# nano-master.net
KiCad netlist of a schematic drawn in EAGLE
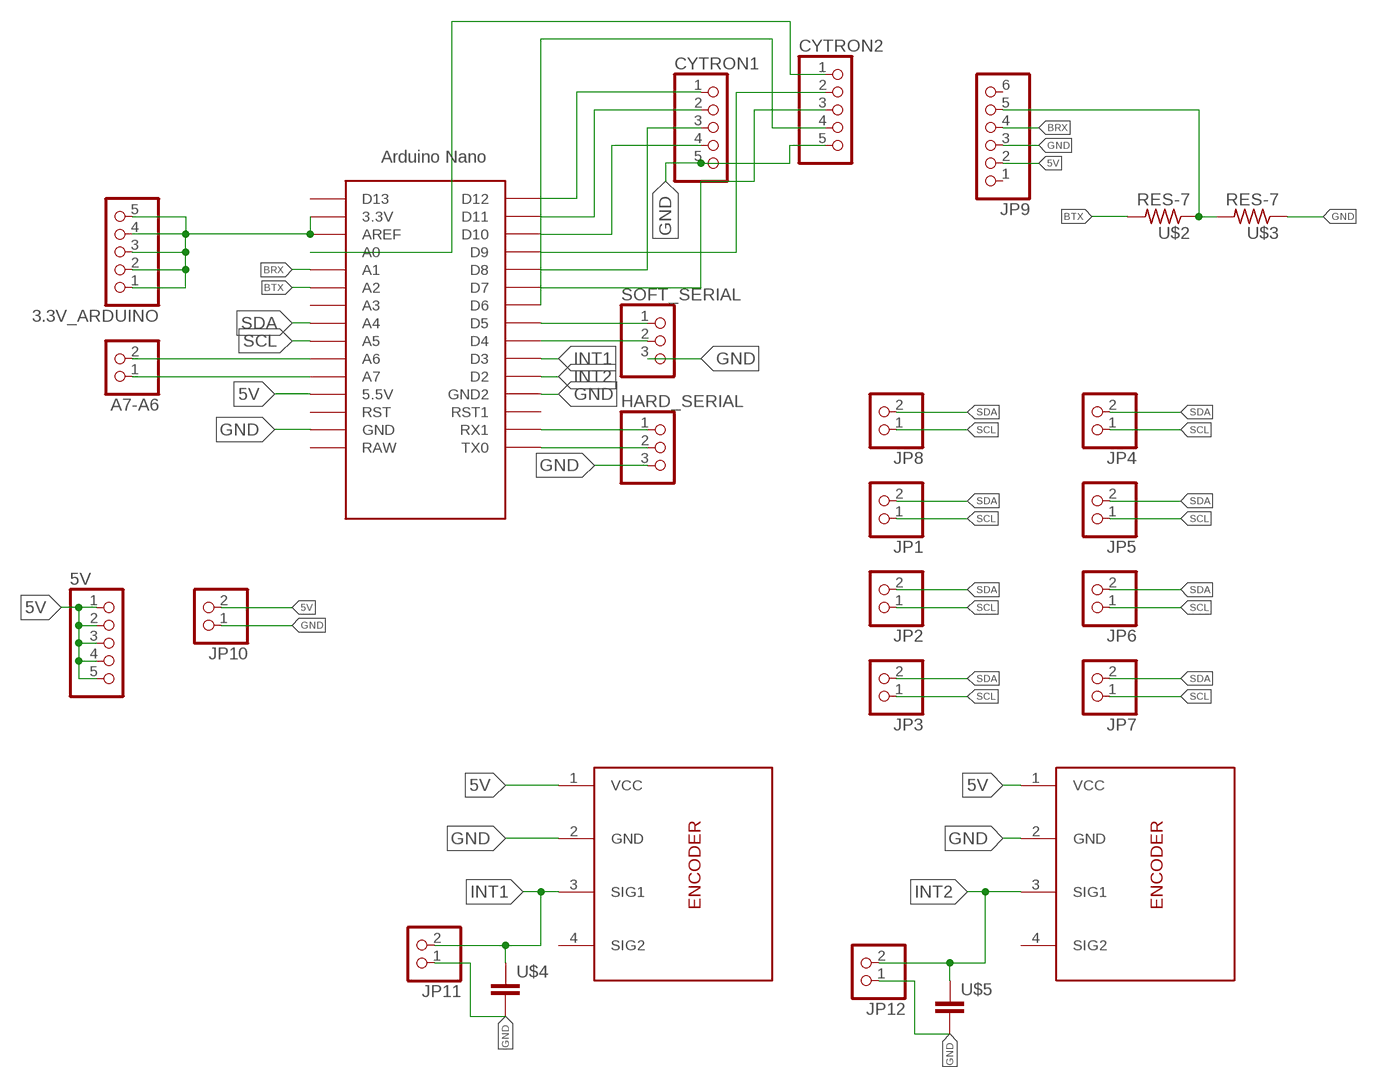
[diagram p0: schematic, sheet 1]

(export (version "E")
  (design (tool "Eeschema 10.0.6"))
  (components
    (comp (ref "3.3V_ARDUINO")
      (value "PINHD-1X5")
      (footprint "eagle-import:1X05")
      (libsource (lib "eagle-import") (part "PINHD-1X5"))
    )
    (comp (ref "5V")
      (value "PINHD-1X5")
      (footprint "eagle-import:1X05")
      (libsource (lib "eagle-import") (part "PINHD-1X5"))
    )
    (comp (ref "A7-A6")
      (value "PINHD-1X2")
      (footprint "eagle-import:1X02")
      (libsource (lib "eagle-import") (part "PINHD-1X2"))
    )
    (comp (ref "CYTRON1")
      (value "PINHD-1X5")
      (footprint "eagle-import:1X05")
      (libsource (lib "eagle-import") (part "PINHD-1X5"))
    )
    (comp (ref "CYTRON2")
      (value "PINHD-1X5")
      (footprint "eagle-import:1X05")
      (libsource (lib "eagle-import") (part "PINHD-1X5"))
    )
    (comp (ref "ENCODER1")
      (value "ENCODER")
      (footprint "eagle-import:1X04_DATA")
      (libsource (lib "eagle-import") (part "ENCODER"))
    )
    (comp (ref "ENCODER2")
      (value "ENCODER")
      (footprint "eagle-import:1X04_DATA")
      (libsource (lib "eagle-import") (part "ENCODER"))
    )
    (comp (ref "HARD_SERIAL")
      (value "PINHD-1X3")
      (footprint "eagle-import:1X03")
      (libsource (lib "eagle-import") (part "PINHD-1X3"))
    )
    (comp (ref "JP1")
      (value "PINHD-1X2")
      (footprint "eagle-import:1X02")
      (libsource (lib "eagle-import") (part "PINHD-1X2"))
    )
    (comp (ref "JP2")
      (value "PINHD-1X2")
      (footprint "eagle-import:1X02")
      (libsource (lib "eagle-import") (part "PINHD-1X2"))
    )
    (comp (ref "JP3")
      (value "PINHD-1X2")
      (footprint "eagle-import:1X02")
      (libsource (lib "eagle-import") (part "PINHD-1X2"))
    )
    (comp (ref "JP4")
      (value "PINHD-1X2")
      (footprint "eagle-import:1X02")
      (libsource (lib "eagle-import") (part "PINHD-1X2"))
    )
    (comp (ref "JP5")
      (value "PINHD-1X2")
      (footprint "eagle-import:1X02")
      (libsource (lib "eagle-import") (part "PINHD-1X2"))
    )
    (comp (ref "JP6")
      (value "PINHD-1X2")
      (footprint "eagle-import:1X02")
      (libsource (lib "eagle-import") (part "PINHD-1X2"))
    )
    (comp (ref "JP7")
      (value "PINHD-1X2")
      (footprint "eagle-import:1X02")
      (libsource (lib "eagle-import") (part "PINHD-1X2"))
    )
    (comp (ref "JP8")
      (value "PINHD-1X2")
      (footprint "eagle-import:1X02")
      (libsource (lib "eagle-import") (part "PINHD-1X2"))
    )
    (comp (ref "JP9")
      (value "PINHD-1X6")
      (footprint "eagle-import:1X06")
      (libsource (lib "eagle-import") (part "PINHD-1X6"))
    )
    (comp (ref "JP10")
      (value "PINHD-1X2")
      (footprint "eagle-import:1X02")
      (libsource (lib "eagle-import") (part "PINHD-1X2"))
    )
    (comp (ref "JP11")
      (value "PINHD-1X2")
      (footprint "eagle-import:1X02")
      (libsource (lib "eagle-import") (part "PINHD-1X2"))
    )
    (comp (ref "JP12")
      (value "PINHD-1X2")
      (footprint "eagle-import:1X02")
      (libsource (lib "eagle-import") (part "PINHD-1X2"))
    )
    (comp (ref "SOFT_SERIAL")
      (value "PINHD-1X3")
      (footprint "eagle-import:1X03")
      (libsource (lib "eagle-import") (part "PINHD-1X3"))
    )
    (comp (ref "U$1")
      (value "ARDUINO_NANO")
      (footprint "eagle-import:NANO")
      (libsource (lib "eagle-import") (part "ARDUINO_NANO"))
    )
    (comp (ref "U$2")
      (value "RES-7")
      (footprint "eagle-import:0204_7")
      (libsource (lib "eagle-import") (part "RES-7"))
    )
    (comp (ref "U$3")
      (value "RES-7")
      (footprint "eagle-import:0204_7")
      (libsource (lib "eagle-import") (part "RES-7"))
    )
    (comp (ref "U$4")
      (value "CAPACITOR")
      (footprint "eagle-import:C025-025X050")
      (libsource (lib "eagle-import") (part "CAPACITOR"))
    )
    (comp (ref "U$5")
      (value "CAPACITOR")
      (footprint "eagle-import:C025-025X050")
      (libsource (lib "eagle-import") (part "CAPACITOR"))
    )
  )
  (nets
    (net (code "1") (name "5V") (class "Default")
      (node (ref "5V") (pin "1") (pinfunction "1_1") (pintype "passive"))
      (node (ref "5V") (pin "2") (pinfunction "2_2") (pintype "passive"))
      (node (ref "5V") (pin "3") (pinfunction "3_3") (pintype "passive"))
      (node (ref "5V") (pin "4") (pinfunction "4_4") (pintype "passive"))
      (node (ref "5V") (pin "5") (pinfunction "5_5") (pintype "passive"))
      (node (ref "ENCODER1") (pin "1") (pinfunction "VCC_1") (pintype "bidirectional"))
      (node (ref "ENCODER2") (pin "1") (pinfunction "VCC_1") (pintype "bidirectional"))
      (node (ref "JP10") (pin "2") (pinfunction "2_2") (pintype "passive"))
      (node (ref "JP9") (pin "2") (pinfunction "2_2") (pintype "passive"))
      (node (ref "U$1") (pin "5V") (pinfunction "5.5V_5V") (pintype "bidirectional"))
    )
    (net (code "2") (name "BRX") (class "Default")
      (node (ref "JP9") (pin "4") (pinfunction "4_4") (pintype "passive"))
      (node (ref "U$1") (pin "A1") (pinfunction "A1_A1") (pintype "bidirectional"))
    )
    (net (code "3") (name "BTX") (class "Default")
      (node (ref "U$1") (pin "A2") (pinfunction "A2_A2") (pintype "bidirectional"))
      (node (ref "U$2") (pin "2") (pinfunction "2_2") (pintype "passive"))
    )
    (net (code "4") (name "GND") (class "Default")
      (node (ref "CYTRON1") (pin "5") (pinfunction "5_5") (pintype "passive"))
      (node (ref "CYTRON2") (pin "5") (pinfunction "5_5") (pintype "passive"))
      (node (ref "ENCODER1") (pin "2") (pinfunction "GND_2") (pintype "bidirectional"))
      (node (ref "ENCODER2") (pin "2") (pinfunction "GND_2") (pintype "bidirectional"))
      (node (ref "HARD_SERIAL") (pin "3") (pinfunction "3_3") (pintype "passive"))
      (node (ref "JP10") (pin "1") (pinfunction "1_1") (pintype "passive"))
      (node (ref "JP11") (pin "1") (pinfunction "1_1") (pintype "passive"))
      (node (ref "JP12") (pin "1") (pinfunction "1_1") (pintype "passive"))
      (node (ref "JP9") (pin "3") (pinfunction "3_3") (pintype "passive"))
      (node (ref "SOFT_SERIAL") (pin "3") (pinfunction "3_3") (pintype "passive"))
      (node (ref "U$1") (pin "GND") (pinfunction "GND_GND") (pintype "bidirectional"))
      (node (ref "U$1") (pin "GND1") (pinfunction "GND2_GND1") (pintype "bidirectional"))
      (node (ref "U$3") (pin "1") (pinfunction "1_1") (pintype "passive"))
      (node (ref "U$4") (pin "2") (pinfunction "2_2") (pintype "passive"))
      (node (ref "U$5") (pin "2") (pinfunction "2_2") (pintype "passive"))
    )
    (net (code "5") (name "INT1") (class "Default")
      (node (ref "ENCODER2") (pin "3") (pinfunction "SIG1_3") (pintype "bidirectional"))
      (node (ref "JP11") (pin "2") (pinfunction "2_2") (pintype "passive"))
      (node (ref "U$1") (pin "D3") (pinfunction "D3_D3") (pintype "bidirectional"))
      (node (ref "U$4") (pin "1") (pinfunction "1_1") (pintype "passive"))
    )
    (net (code "6") (name "INT2") (class "Default")
      (node (ref "ENCODER1") (pin "3") (pinfunction "SIG1_3") (pintype "bidirectional"))
      (node (ref "JP12") (pin "2") (pinfunction "2_2") (pintype "passive"))
      (node (ref "U$1") (pin "D2") (pinfunction "D2_D2") (pintype "bidirectional"))
      (node (ref "U$5") (pin "1") (pinfunction "1_1") (pintype "passive"))
    )
    (net (code "7") (name "Net-(3.3V_ARDUINO-Pad1)") (class "Default")
      (node (ref "3.3V_ARDUINO") (pin "1") (pinfunction "1_1") (pintype "passive"))
      (node (ref "3.3V_ARDUINO") (pin "2") (pinfunction "2_2") (pintype "passive"))
      (node (ref "3.3V_ARDUINO") (pin "3") (pinfunction "3_3") (pintype "passive"))
      (node (ref "3.3V_ARDUINO") (pin "4") (pinfunction "4_4") (pintype "passive"))
      (node (ref "3.3V_ARDUINO") (pin "5") (pinfunction "5_5") (pintype "passive"))
      (node (ref "U$1") (pin "3.3V") (pinfunction "3.3V_3.3V") (pintype "bidirectional"))
      (node (ref "U$1") (pin "AREF") (pinfunction "AREF_AREF") (pintype "bidirectional"))
    )
    (net (code "8") (name "Net-(A7-A6-Pad1)") (class "Default")
      (node (ref "A7-A6") (pin "1") (pinfunction "1_1") (pintype "passive"))
      (node (ref "U$1") (pin "A7") (pinfunction "A7_A7") (pintype "bidirectional"))
    )
    (net (code "9") (name "Net-(A7-A6-Pad2)") (class "Default")
      (node (ref "A7-A6") (pin "2") (pinfunction "2_2") (pintype "passive"))
      (node (ref "U$1") (pin "A6") (pinfunction "A6_A6") (pintype "bidirectional"))
    )
    (net (code "10") (name "Net-(CYTRON1-Pad1)") (class "Default")
      (node (ref "CYTRON1") (pin "1") (pinfunction "1_1") (pintype "passive"))
      (node (ref "U$1") (pin "D12") (pinfunction "D12_D12") (pintype "bidirectional"))
    )
    (net (code "11") (name "Net-(CYTRON1-Pad2)") (class "Default")
      (node (ref "CYTRON1") (pin "2") (pinfunction "2_2") (pintype "passive"))
      (node (ref "U$1") (pin "D11") (pinfunction "D11_D11") (pintype "bidirectional"))
    )
    (net (code "12") (name "Net-(CYTRON1-Pad3)") (class "Default")
      (node (ref "CYTRON1") (pin "3") (pinfunction "3_3") (pintype "passive"))
      (node (ref "U$1") (pin "D8") (pinfunction "D8_D8") (pintype "bidirectional"))
    )
    (net (code "13") (name "Net-(CYTRON1-Pad4)") (class "Default")
      (node (ref "CYTRON1") (pin "4") (pinfunction "4_4") (pintype "passive"))
      (node (ref "U$1") (pin "D10") (pinfunction "D10_D10") (pintype "bidirectional"))
    )
    (net (code "14") (name "Net-(CYTRON2-Pad1)") (class "Default")
      (node (ref "CYTRON2") (pin "1") (pinfunction "1_1") (pintype "passive"))
      (node (ref "U$1") (pin "A0") (pinfunction "A0_A0") (pintype "bidirectional"))
    )
    (net (code "15") (name "Net-(CYTRON2-Pad2)") (class "Default")
      (node (ref "CYTRON2") (pin "2") (pinfunction "2_2") (pintype "passive"))
      (node (ref "U$1") (pin "D9") (pinfunction "D9_D9") (pintype "bidirectional"))
    )
    (net (code "16") (name "Net-(CYTRON2-Pad3)") (class "Default")
      (node (ref "CYTRON2") (pin "3") (pinfunction "3_3") (pintype "passive"))
      (node (ref "U$1") (pin "D7") (pinfunction "D7_D7") (pintype "bidirectional"))
    )
    (net (code "17") (name "Net-(CYTRON2-Pad4)") (class "Default")
      (node (ref "CYTRON2") (pin "4") (pinfunction "4_4") (pintype "passive"))
      (node (ref "U$1") (pin "D6") (pinfunction "D6_D6") (pintype "bidirectional"))
    )
    (net (code "18") (name "Net-(HARD_SERIAL-Pad1)") (class "Default")
      (node (ref "HARD_SERIAL") (pin "1") (pinfunction "1_1") (pintype "passive"))
      (node (ref "U$1") (pin "RX1") (pinfunction "RX1_RX1") (pintype "bidirectional"))
    )
    (net (code "19") (name "Net-(HARD_SERIAL-Pad2)") (class "Default")
      (node (ref "HARD_SERIAL") (pin "2") (pinfunction "2_2") (pintype "passive"))
      (node (ref "U$1") (pin "TX0") (pinfunction "TX0_TX0") (pintype "bidirectional"))
    )
    (net (code "20") (name "Net-(JP9-Pad5)") (class "Default")
      (node (ref "JP9") (pin "5") (pinfunction "5_5") (pintype "passive"))
      (node (ref "U$2") (pin "1") (pinfunction "1_1") (pintype "passive"))
      (node (ref "U$3") (pin "2") (pinfunction "2_2") (pintype "passive"))
    )
    (net (code "21") (name "Net-(SOFT_SERIAL-Pad1)") (class "Default")
      (node (ref "SOFT_SERIAL") (pin "1") (pinfunction "1_1") (pintype "passive"))
      (node (ref "U$1") (pin "D5") (pinfunction "D5_D5") (pintype "bidirectional"))
    )
    (net (code "22") (name "Net-(SOFT_SERIAL-Pad2)") (class "Default")
      (node (ref "SOFT_SERIAL") (pin "2") (pinfunction "2_2") (pintype "passive"))
      (node (ref "U$1") (pin "D4") (pinfunction "D4_D4") (pintype "bidirectional"))
    )
    (net (code "23") (name "SCL") (class "Default")
      (node (ref "JP1") (pin "1") (pinfunction "1_1") (pintype "passive"))
      (node (ref "JP2") (pin "1") (pinfunction "1_1") (pintype "passive"))
      (node (ref "JP3") (pin "1") (pinfunction "1_1") (pintype "passive"))
      (node (ref "JP4") (pin "1") (pinfunction "1_1") (pintype "passive"))
      (node (ref "JP5") (pin "1") (pinfunction "1_1") (pintype "passive"))
      (node (ref "JP6") (pin "1") (pinfunction "1_1") (pintype "passive"))
      (node (ref "JP7") (pin "1") (pinfunction "1_1") (pintype "passive"))
      (node (ref "JP8") (pin "1") (pinfunction "1_1") (pintype "passive"))
      (node (ref "U$1") (pin "A5") (pinfunction "A5_A5") (pintype "bidirectional"))
    )
    (net (code "24") (name "SDA") (class "Default")
      (node (ref "JP1") (pin "2") (pinfunction "2_2") (pintype "passive"))
      (node (ref "JP2") (pin "2") (pinfunction "2_2") (pintype "passive"))
      (node (ref "JP3") (pin "2") (pinfunction "2_2") (pintype "passive"))
      (node (ref "JP4") (pin "2") (pinfunction "2_2") (pintype "passive"))
      (node (ref "JP5") (pin "2") (pinfunction "2_2") (pintype "passive"))
      (node (ref "JP6") (pin "2") (pinfunction "2_2") (pintype "passive"))
      (node (ref "JP7") (pin "2") (pinfunction "2_2") (pintype "passive"))
      (node (ref "JP8") (pin "2") (pinfunction "2_2") (pintype "passive"))
      (node (ref "U$1") (pin "A4") (pinfunction "A4_A4") (pintype "bidirectional"))
    )
    (net (code "25") (name "unconnected-(ENCODER1-SIG2-Pad4)") (class "Default")
      (node (ref "ENCODER1") (pin "4") (pinfunction "SIG2_4") (pintype "bidirectional"))
    )
    (net (code "26") (name "unconnected-(ENCODER2-SIG2-Pad4)") (class "Default")
      (node (ref "ENCODER2") (pin "4") (pinfunction "SIG2_4") (pintype "bidirectional"))
    )
    (net (code "27") (name "unconnected-(JP9-Pad1)") (class "Default")
      (node (ref "JP9") (pin "1") (pinfunction "1_1") (pintype "passive"))
    )
    (net (code "28") (name "unconnected-(JP9-Pad6)") (class "Default")
      (node (ref "JP9") (pin "6") (pinfunction "6_6") (pintype "passive"))
    )
    (net (code "29") (name "unconnected-(U$1-PadA3)") (class "Default")
      (node (ref "U$1") (pin "A3") (pinfunction "A3_A3") (pintype "bidirectional"))
    )
    (net (code "30") (name "unconnected-(U$1-PadD13)") (class "Default")
      (node (ref "U$1") (pin "D13") (pinfunction "D13_D13") (pintype "bidirectional"))
    )
    (net (code "31") (name "unconnected-(U$1-PadRAW)") (class "Default")
      (node (ref "U$1") (pin "RAW") (pinfunction "RAW_RAW") (pintype "bidirectional"))
    )
    (net (code "32") (name "unconnected-(U$1-PadRST)") (class "Default")
      (node (ref "U$1") (pin "RST") (pinfunction "RST_RST") (pintype "bidirectional"))
    )
    (net (code "33") (name "unconnected-(U$1-PadRST1)") (class "Default")
      (node (ref "U$1") (pin "RST1") (pinfunction "RST1_RST1") (pintype "bidirectional"))
    )
  )
)
